# FPGA_sdram.net
KiCad netlist of a schematic drawn in Altium Designer
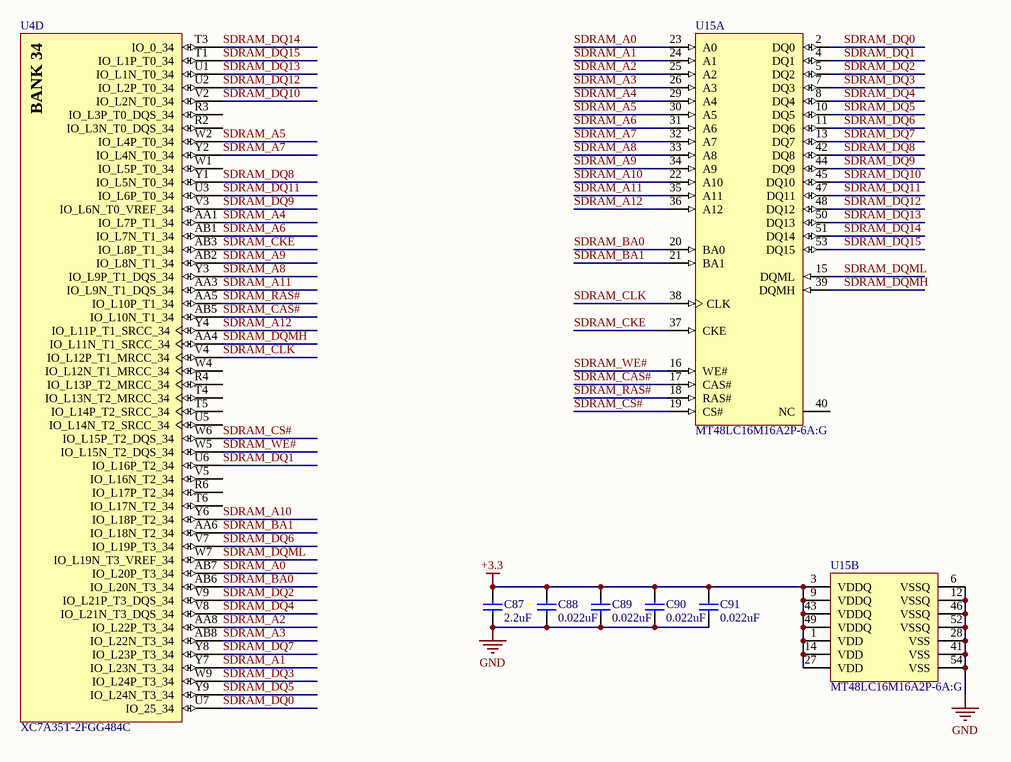
[diagram p0: FPGA sdram.SchDoc]

(export (version "E")
  (design (tool "Eeschema 10.0.6"))
  (components
    (comp (ref "C87")
      (value "2.2uF")
      (footprint "CAPC1005X06L")
      (description "CAP CER 2.2UF 10V X5R 0402")
      (fields
        (field (name "PARTNUMBER") "GRM155R61A225KE95D")
        (field (name "DIGI-KEY PART NUMBER") "490-10451-1-ND")
      )
      (libsource (lib "cap_murata") (part "CAPACITOR"))
    )
    (comp (ref "C88")
      (value "0.022uF")
      (footprint "CAPC1005X06L")
      (description "CAP CER 0.022UF 10V X5R 0402")
      (fields
        (field (name "PARTNUMBER") "GRM155R61A223KA01D")
        (field (name "DIGI-KEY PART NUMBER") "490-6302-1-ND")
      )
      (libsource (lib "cap_murata") (part "CAPACITOR"))
    )
    (comp (ref "C89")
      (value "0.022uF")
      (footprint "CAPC1005X06L")
      (description "CAP CER 0.022UF 10V X5R 0402")
      (fields
        (field (name "PARTNUMBER") "GRM155R61A223KA01D")
        (field (name "DIGI-KEY PART NUMBER") "490-6302-1-ND")
      )
      (libsource (lib "cap_murata") (part "CAPACITOR"))
    )
    (comp (ref "C90")
      (value "0.022uF")
      (footprint "CAPC1005X06L")
      (description "CAP CER 0.022UF 10V X5R 0402")
      (fields
        (field (name "PARTNUMBER") "GRM155R61A223KA01D")
        (field (name "DIGI-KEY PART NUMBER") "490-6302-1-ND")
      )
      (libsource (lib "cap_murata") (part "CAPACITOR"))
    )
    (comp (ref "C91")
      (value "0.022uF")
      (footprint "CAPC1005X06L")
      (description "CAP CER 0.022UF 10V X5R 0402")
      (fields
        (field (name "PARTNUMBER") "GRM155R61A223KA01D")
        (field (name "DIGI-KEY PART NUMBER") "490-6302-1-ND")
      )
      (libsource (lib "cap_murata") (part "CAPACITOR"))
    )
    (comp (ref "U4")
      (value "XC7A35T-2FGG484C")
      (footprint "FGG484")
      (description "Artix-7 FPGA, 250 User I/Os, 4 GTP, 484-Ball BGA, Speed Grade 2, Commercial Grade, Pb-Free")
      (fields (field (name "MANUFACTURER") "Xilinx"))
      (libsource (lib "Altium Content Vault") (part "XLNX-XC7A35T-FGG484"))
    )
    (comp (ref "U15")
      (value "MT48LC16M16A2P-6A:G")
      (footprint "MICT-TG-54_M")
      (description "256 Mb PC133 SDR SDRAM, 16 Mb x 16, 3 to 3.6 V, 0 to 70 degC, 54-Pin TSOP (TG), Pb-Free")
      (fields (field (name "MANUFACTURER") "Micron"))
      (libsource (lib "Altium Content Vault") (part "MICT-MT48LC16M16A2P-54"))
    )
  )
  (nets
    (net (code "1") (name "+3.3") (class "Default")
      (node (ref "C87") (pin "1") (pinfunction "1_1") (pintype "passive"))
      (node (ref "C88") (pin "1") (pinfunction "1_1") (pintype "passive"))
      (node (ref "C89") (pin "1") (pinfunction "1_1") (pintype "passive"))
      (node (ref "C90") (pin "1") (pinfunction "1_1") (pintype "passive"))
      (node (ref "C91") (pin "1") (pinfunction "1_1") (pintype "passive"))
      (node (ref "U15") (pin "1") (pinfunction "VDD_1") (pintype "power_in"))
      (node (ref "U15") (pin "14") (pinfunction "VDD_14") (pintype "power_in"))
      (node (ref "U15") (pin "27") (pinfunction "VDD_27") (pintype "power_in"))
      (node (ref "U15") (pin "3") (pinfunction "VDDQ_3") (pintype "power_in"))
      (node (ref "U15") (pin "43") (pinfunction "VDDQ_43") (pintype "power_in"))
      (node (ref "U15") (pin "49") (pinfunction "VDDQ_49") (pintype "power_in"))
      (node (ref "U15") (pin "9") (pinfunction "VDDQ_9") (pintype "power_in"))
    )
    (net (code "2") (name "/SDRAM_A0") (class "Default")
      (node (ref "U15") (pin "23") (pinfunction "A0_23") (pintype "input"))
      (node (ref "U4") (pin "AB7") (pinfunction "IO_L20P_T3_34_AB7") (pintype "bidirectional"))
    )
    (net (code "3") (name "/SDRAM_A1") (class "Default")
      (node (ref "U15") (pin "24") (pinfunction "A1_24") (pintype "input"))
      (node (ref "U4") (pin "Y7") (pinfunction "IO_L23N_T3_34_Y7") (pintype "bidirectional"))
    )
    (net (code "4") (name "/SDRAM_A2") (class "Default")
      (node (ref "U15") (pin "25") (pinfunction "A2_25") (pintype "input"))
      (node (ref "U4") (pin "AA8") (pinfunction "IO_L22P_T3_34_AA8") (pintype "bidirectional"))
    )
    (net (code "5") (name "/SDRAM_A3") (class "Default")
      (node (ref "U15") (pin "26") (pinfunction "A3_26") (pintype "input"))
      (node (ref "U4") (pin "AB8") (pinfunction "IO_L22N_T3_34_AB8") (pintype "bidirectional"))
    )
    (net (code "6") (name "/SDRAM_A4") (class "Default")
      (node (ref "U15") (pin "29") (pinfunction "A4_29") (pintype "input"))
      (node (ref "U4") (pin "AA1") (pinfunction "IO_L7P_T1_34_AA1") (pintype "bidirectional"))
    )
    (net (code "7") (name "/SDRAM_A5") (class "Default")
      (node (ref "U15") (pin "30") (pinfunction "A5_30") (pintype "input"))
      (node (ref "U4") (pin "W2") (pinfunction "IO_L4P_T0_34_W2") (pintype "bidirectional"))
    )
    (net (code "8") (name "/SDRAM_A6") (class "Default")
      (node (ref "U15") (pin "31") (pinfunction "A6_31") (pintype "input"))
      (node (ref "U4") (pin "AB1") (pinfunction "IO_L7N_T1_34_AB1") (pintype "bidirectional"))
    )
    (net (code "9") (name "/SDRAM_A7") (class "Default")
      (node (ref "U15") (pin "32") (pinfunction "A7_32") (pintype "input"))
      (node (ref "U4") (pin "Y2") (pinfunction "IO_L4N_T0_34_Y2") (pintype "bidirectional"))
    )
    (net (code "10") (name "/SDRAM_A8") (class "Default")
      (node (ref "U15") (pin "33") (pinfunction "A8_33") (pintype "input"))
      (node (ref "U4") (pin "Y3") (pinfunction "IO_L9P_T1_DQS_34_Y3") (pintype "bidirectional"))
    )
    (net (code "11") (name "/SDRAM_A9") (class "Default")
      (node (ref "U15") (pin "34") (pinfunction "A9_34") (pintype "input"))
      (node (ref "U4") (pin "AB2") (pinfunction "IO_L8N_T1_34_AB2") (pintype "bidirectional"))
    )
    (net (code "12") (name "/SDRAM_A10") (class "Default")
      (node (ref "U15") (pin "22") (pinfunction "A10_22") (pintype "input"))
      (node (ref "U4") (pin "Y6") (pinfunction "IO_L18P_T2_34_Y6") (pintype "bidirectional"))
    )
    (net (code "13") (name "/SDRAM_A11") (class "Default")
      (node (ref "U15") (pin "35") (pinfunction "A11_35") (pintype "input"))
      (node (ref "U4") (pin "AA3") (pinfunction "IO_L9N_T1_DQS_34_AA3") (pintype "bidirectional"))
    )
    (net (code "14") (name "/SDRAM_A12") (class "Default")
      (node (ref "U15") (pin "36") (pinfunction "A12_36") (pintype "input"))
      (node (ref "U4") (pin "Y4") (pinfunction "IO_L11P_T1_SRCC_34_Y4") (pintype "bidirectional"))
    )
    (net (code "15") (name "/SDRAM_BA0") (class "Default")
      (node (ref "U15") (pin "20") (pinfunction "BA0_20") (pintype "input"))
      (node (ref "U4") (pin "AB6") (pinfunction "IO_L20N_T3_34_AB6") (pintype "bidirectional"))
    )
    (net (code "16") (name "/SDRAM_BA1") (class "Default")
      (node (ref "U15") (pin "21") (pinfunction "BA1_21") (pintype "input"))
      (node (ref "U4") (pin "AA6") (pinfunction "IO_L18N_T2_34_AA6") (pintype "bidirectional"))
    )
    (net (code "17") (name "/SDRAM_CAS#") (class "Default")
      (node (ref "U15") (pin "17") (pinfunction "CAS#_17") (pintype "input"))
      (node (ref "U4") (pin "AB5") (pinfunction "IO_L10N_T1_34_AB5") (pintype "bidirectional"))
    )
    (net (code "18") (name "/SDRAM_CKE") (class "Default")
      (node (ref "U15") (pin "37") (pinfunction "CKE_37") (pintype "input"))
      (node (ref "U4") (pin "AB3") (pinfunction "IO_L8P_T1_34_AB3") (pintype "bidirectional"))
    )
    (net (code "19") (name "/SDRAM_CLK") (class "Default")
      (node (ref "U15") (pin "38") (pinfunction "CLK_38") (pintype "input"))
      (node (ref "U4") (pin "V4") (pinfunction "IO_L12P_T1_MRCC_34_V4") (pintype "bidirectional"))
    )
    (net (code "20") (name "/SDRAM_CS#") (class "Default")
      (node (ref "U15") (pin "19") (pinfunction "CS#_19") (pintype "input"))
      (node (ref "U4") (pin "W6") (pinfunction "IO_L15P_T2_DQS_34_W6") (pintype "bidirectional"))
    )
    (net (code "21") (name "/SDRAM_DQ0") (class "Default")
      (node (ref "U15") (pin "2") (pinfunction "DQ0_2") (pintype "bidirectional"))
      (node (ref "U4") (pin "U7") (pinfunction "IO_25_34_U7") (pintype "bidirectional"))
    )
    (net (code "22") (name "/SDRAM_DQ1") (class "Default")
      (node (ref "U15") (pin "4") (pinfunction "DQ1_4") (pintype "bidirectional"))
      (node (ref "U4") (pin "U6") (pinfunction "IO_L16P_T2_34_U6") (pintype "bidirectional"))
    )
    (net (code "23") (name "/SDRAM_DQ2") (class "Default")
      (node (ref "U15") (pin "5") (pinfunction "DQ2_5") (pintype "bidirectional"))
      (node (ref "U4") (pin "V9") (pinfunction "IO_L21P_T3_DQS_34_V9") (pintype "bidirectional"))
    )
    (net (code "24") (name "/SDRAM_DQ3") (class "Default")
      (node (ref "U15") (pin "7") (pinfunction "DQ3_7") (pintype "bidirectional"))
      (node (ref "U4") (pin "W9") (pinfunction "IO_L24P_T3_34_W9") (pintype "bidirectional"))
    )
    (net (code "25") (name "/SDRAM_DQ4") (class "Default")
      (node (ref "U15") (pin "8") (pinfunction "DQ4_8") (pintype "bidirectional"))
      (node (ref "U4") (pin "V8") (pinfunction "IO_L21N_T3_DQS_34_V8") (pintype "bidirectional"))
    )
    (net (code "26") (name "/SDRAM_DQ5") (class "Default")
      (node (ref "U15") (pin "10") (pinfunction "DQ5_10") (pintype "bidirectional"))
      (node (ref "U4") (pin "Y9") (pinfunction "IO_L24N_T3_34_Y9") (pintype "bidirectional"))
    )
    (net (code "27") (name "/SDRAM_DQ6") (class "Default")
      (node (ref "U15") (pin "11") (pinfunction "DQ6_11") (pintype "bidirectional"))
      (node (ref "U4") (pin "V7") (pinfunction "IO_L19P_T3_34_V7") (pintype "bidirectional"))
    )
    (net (code "28") (name "/SDRAM_DQ7") (class "Default")
      (node (ref "U15") (pin "13") (pinfunction "DQ7_13") (pintype "bidirectional"))
      (node (ref "U4") (pin "Y8") (pinfunction "IO_L23P_T3_34_Y8") (pintype "bidirectional"))
    )
    (net (code "29") (name "/SDRAM_DQ8") (class "Default")
      (node (ref "U15") (pin "42") (pinfunction "DQ8_42") (pintype "bidirectional"))
      (node (ref "U4") (pin "Y1") (pinfunction "IO_L5N_T0_34_Y1") (pintype "bidirectional"))
    )
    (net (code "30") (name "/SDRAM_DQ9") (class "Default")
      (node (ref "U15") (pin "44") (pinfunction "DQ9_44") (pintype "bidirectional"))
      (node (ref "U4") (pin "V3") (pinfunction "IO_L6N_T0_VREF_34_V3") (pintype "bidirectional"))
    )
    (net (code "31") (name "/SDRAM_DQ10") (class "Default")
      (node (ref "U15") (pin "45") (pinfunction "DQ10_45") (pintype "bidirectional"))
      (node (ref "U4") (pin "V2") (pinfunction "IO_L2N_T0_34_V2") (pintype "bidirectional"))
    )
    (net (code "32") (name "/SDRAM_DQ11") (class "Default")
      (node (ref "U15") (pin "47") (pinfunction "DQ11_47") (pintype "bidirectional"))
      (node (ref "U4") (pin "U3") (pinfunction "IO_L6P_T0_34_U3") (pintype "bidirectional"))
    )
    (net (code "33") (name "/SDRAM_DQ12") (class "Default")
      (node (ref "U15") (pin "48") (pinfunction "DQ12_48") (pintype "bidirectional"))
      (node (ref "U4") (pin "U2") (pinfunction "IO_L2P_T0_34_U2") (pintype "bidirectional"))
    )
    (net (code "34") (name "/SDRAM_DQ13") (class "Default")
      (node (ref "U15") (pin "50") (pinfunction "DQ13_50") (pintype "bidirectional"))
      (node (ref "U4") (pin "U1") (pinfunction "IO_L1N_T0_34_U1") (pintype "bidirectional"))
    )
    (net (code "35") (name "/SDRAM_DQ14") (class "Default")
      (node (ref "U15") (pin "51") (pinfunction "DQ14_51") (pintype "bidirectional"))
      (node (ref "U4") (pin "T3") (pinfunction "IO_0_34_T3") (pintype "bidirectional"))
    )
    (net (code "36") (name "/SDRAM_DQ15") (class "Default")
      (node (ref "U15") (pin "53") (pinfunction "DQ15_53") (pintype "bidirectional"))
      (node (ref "U4") (pin "T1") (pinfunction "IO_L1P_T0_34_T1") (pintype "bidirectional"))
    )
    (net (code "37") (name "/SDRAM_DQMH") (class "Default")
      (node (ref "U15") (pin "39") (pinfunction "DQMH_39") (pintype "input"))
      (node (ref "U4") (pin "AA4") (pinfunction "IO_L11N_T1_SRCC_34_AA4") (pintype "bidirectional"))
    )
    (net (code "38") (name "/SDRAM_DQML") (class "Default")
      (node (ref "U15") (pin "15") (pinfunction "DQML_15") (pintype "input"))
      (node (ref "U4") (pin "W7") (pinfunction "IO_L19N_T3_VREF_34_W7") (pintype "bidirectional"))
    )
    (net (code "39") (name "/SDRAM_RAS#") (class "Default")
      (node (ref "U15") (pin "18") (pinfunction "RAS#_18") (pintype "input"))
      (node (ref "U4") (pin "AA5") (pinfunction "IO_L10P_T1_34_AA5") (pintype "bidirectional"))
    )
    (net (code "40") (name "/SDRAM_WE#") (class "Default")
      (node (ref "U15") (pin "16") (pinfunction "WE#_16") (pintype "input"))
      (node (ref "U4") (pin "W5") (pinfunction "IO_L15N_T2_DQS_34_W5") (pintype "bidirectional"))
    )
    (net (code "41") (name "GND") (class "Default")
      (node (ref "C87") (pin "2") (pinfunction "2_2") (pintype "passive"))
      (node (ref "C88") (pin "2") (pinfunction "2_2") (pintype "passive"))
      (node (ref "C89") (pin "2") (pinfunction "2_2") (pintype "passive"))
      (node (ref "C90") (pin "2") (pinfunction "2_2") (pintype "passive"))
      (node (ref "C91") (pin "2") (pinfunction "2_2") (pintype "passive"))
      (node (ref "U15") (pin "12") (pinfunction "VSSQ_12") (pintype "power_in"))
      (node (ref "U15") (pin "28") (pinfunction "VSS_28") (pintype "power_in"))
      (node (ref "U15") (pin "41") (pinfunction "VSS_41") (pintype "power_in"))
      (node (ref "U15") (pin "46") (pinfunction "VSSQ_46") (pintype "power_in"))
      (node (ref "U15") (pin "52") (pinfunction "VSSQ_52") (pintype "power_in"))
      (node (ref "U15") (pin "54") (pinfunction "VSS_54") (pintype "power_in"))
      (node (ref "U15") (pin "6") (pinfunction "VSSQ_6") (pintype "power_in"))
    )
    (net (code "42") (name "unconnected-(U4D-IO_L3N_T0_DQS_34-PadR2)") (class "Default")
      (node (ref "U4") (pin "R2") (pinfunction "IO_L3N_T0_DQS_34_R2") (pintype "bidirectional"))
    )
    (net (code "43") (name "unconnected-(U4D-IO_L3P_T0_DQS_34-PadR3)") (class "Default")
      (node (ref "U4") (pin "R3") (pinfunction "IO_L3P_T0_DQS_34_R3") (pintype "bidirectional"))
    )
    (net (code "44") (name "unconnected-(U4D-IO_L5P_T0_34-PadW1)") (class "Default")
      (node (ref "U4") (pin "W1") (pinfunction "IO_L5P_T0_34_W1") (pintype "bidirectional"))
    )
    (net (code "45") (name "unconnected-(U4D-IO_L12N_T1_MRCC_34-PadW4)") (class "Default")
      (node (ref "U4") (pin "W4") (pinfunction "IO_L12N_T1_MRCC_34_W4") (pintype "bidirectional"))
    )
    (net (code "46") (name "unconnected-(U4D-IO_L13N_T2_MRCC_34-PadT4)") (class "Default")
      (node (ref "U4") (pin "T4") (pinfunction "IO_L13N_T2_MRCC_34_T4") (pintype "bidirectional"))
    )
    (net (code "47") (name "unconnected-(U4D-IO_L13P_T2_MRCC_34-PadR4)") (class "Default")
      (node (ref "U4") (pin "R4") (pinfunction "IO_L13P_T2_MRCC_34_R4") (pintype "bidirectional"))
    )
    (net (code "48") (name "unconnected-(U4D-IO_L14N_T2_SRCC_34-PadU5)") (class "Default")
      (node (ref "U4") (pin "U5") (pinfunction "IO_L14N_T2_SRCC_34_U5") (pintype "bidirectional"))
    )
    (net (code "49") (name "unconnected-(U4D-IO_L14P_T2_SRCC_34-PadT5)") (class "Default")
      (node (ref "U4") (pin "T5") (pinfunction "IO_L14P_T2_SRCC_34_T5") (pintype "bidirectional"))
    )
    (net (code "50") (name "unconnected-(U4D-IO_L16N_T2_34-PadV5)") (class "Default")
      (node (ref "U4") (pin "V5") (pinfunction "IO_L16N_T2_34_V5") (pintype "bidirectional"))
    )
    (net (code "51") (name "unconnected-(U4D-IO_L17N_T2_34-PadT6)") (class "Default")
      (node (ref "U4") (pin "T6") (pinfunction "IO_L17N_T2_34_T6") (pintype "bidirectional"))
    )
    (net (code "52") (name "unconnected-(U4D-IO_L17P_T2_34-PadR6)") (class "Default")
      (node (ref "U4") (pin "R6") (pinfunction "IO_L17P_T2_34_R6") (pintype "bidirectional"))
    )
    (net (code "53") (name "unconnected-(U15A-NC-Pad40)") (class "Default")
      (node (ref "U15") (pin "40") (pinfunction "NC_40") (pintype "passive"))
    )
  )
)
